# Tray2_BCR.net
KiCad netlist of a schematic drawn in Altium Designer
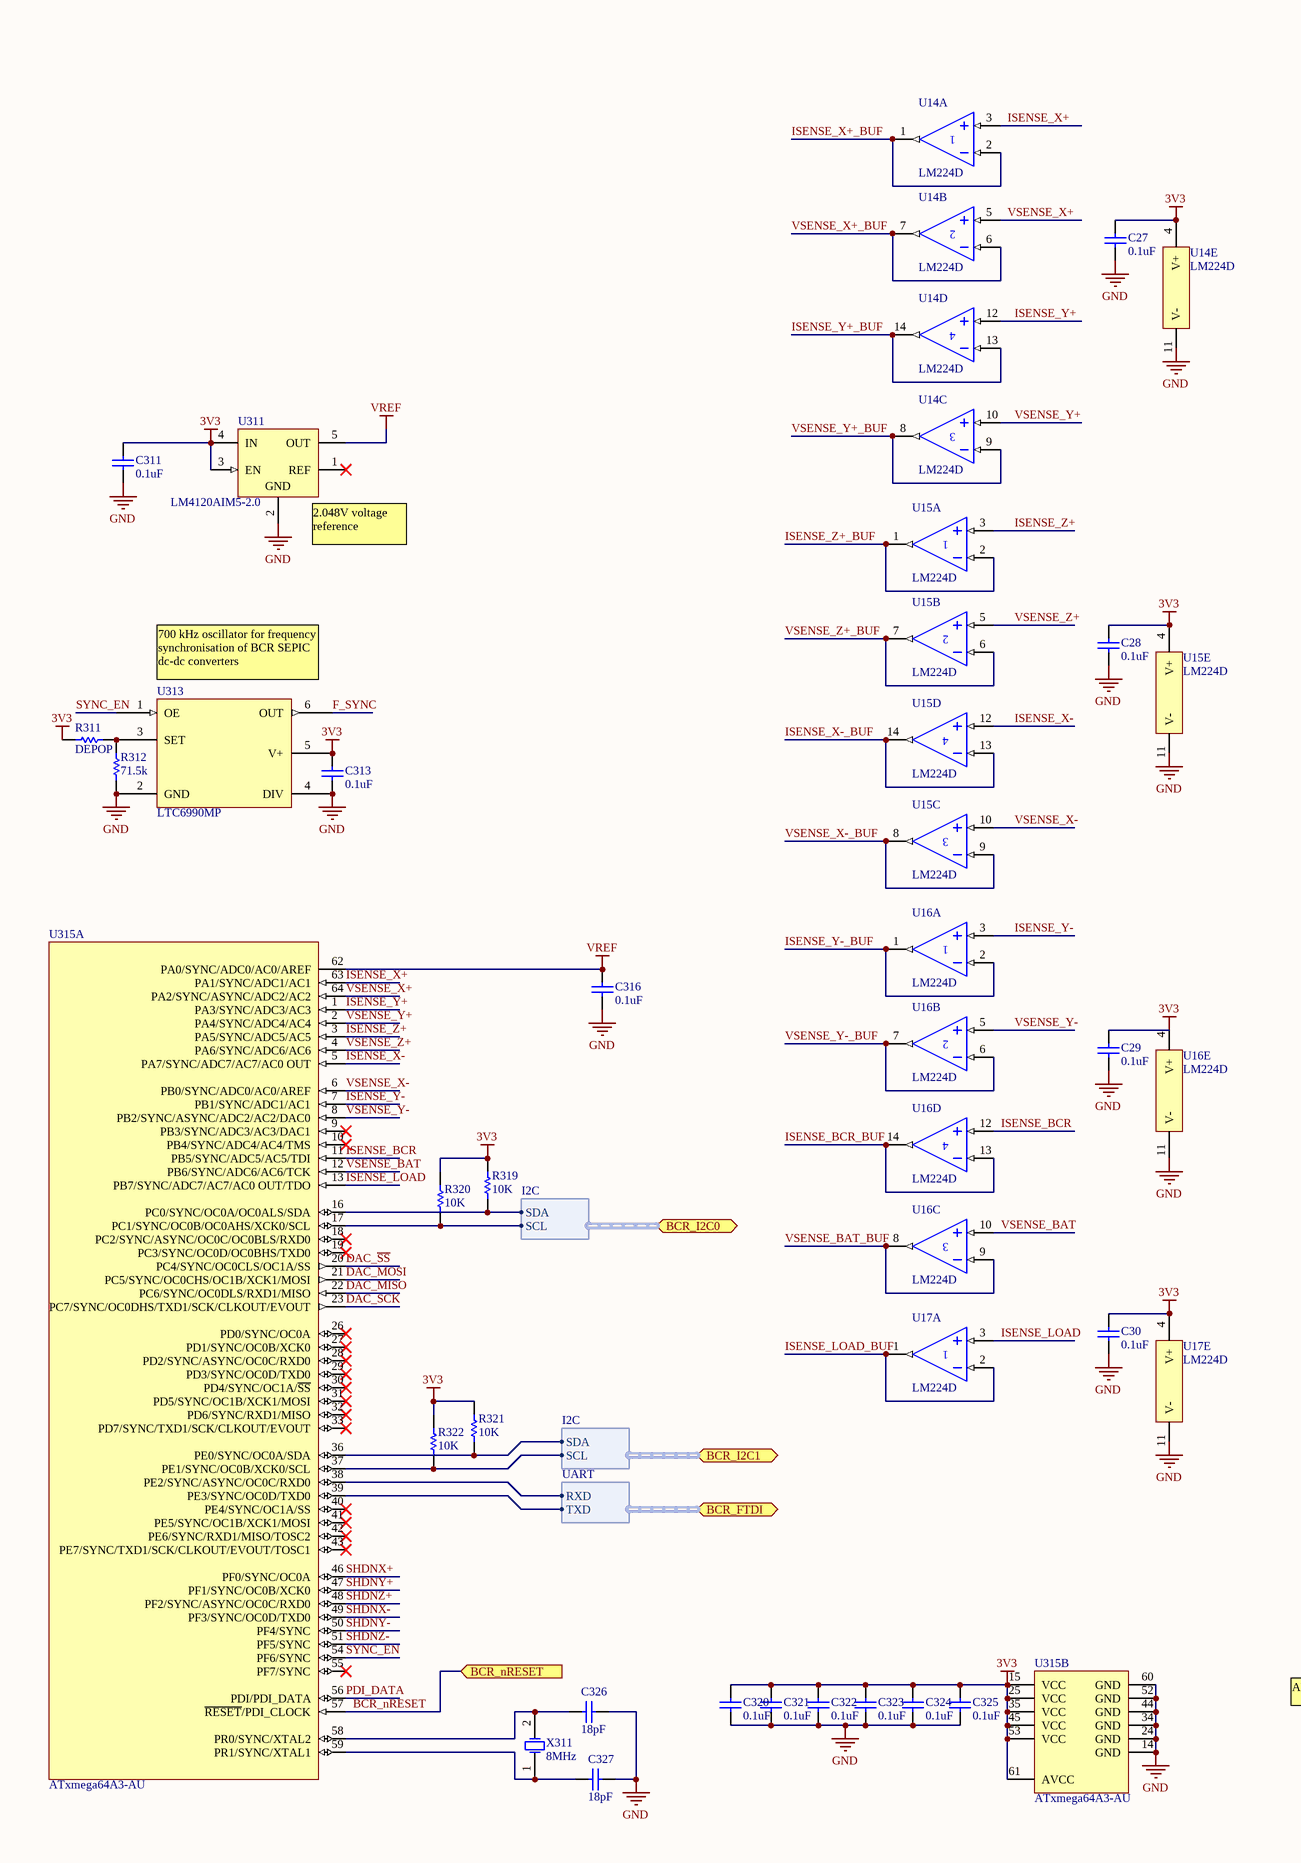
[diagram p0: Tray2_BCR.SchDoc, left]
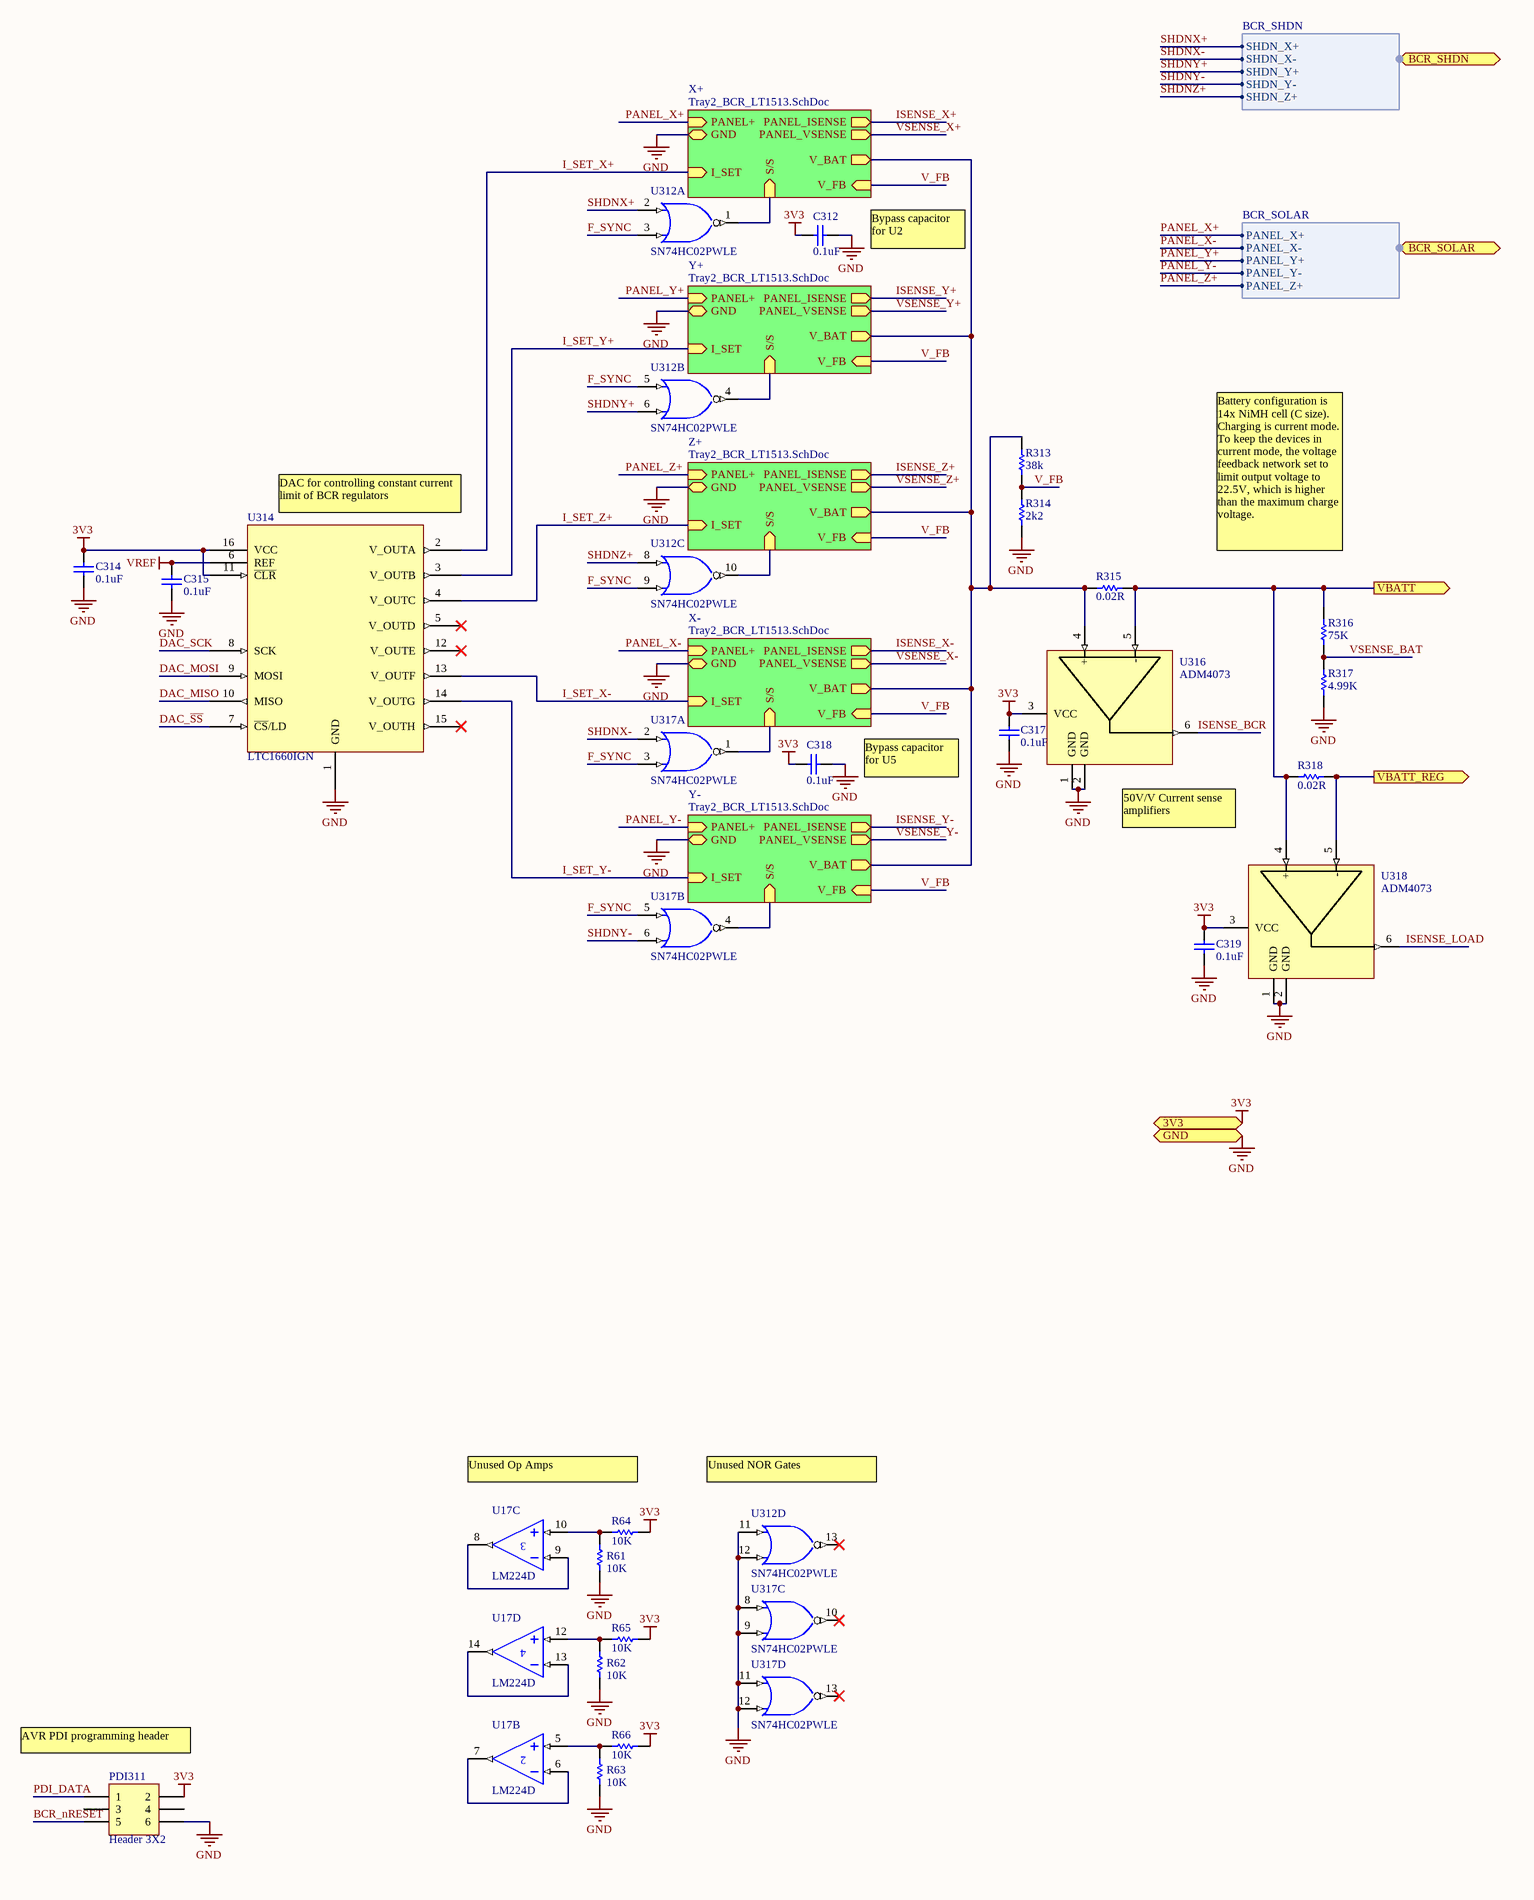
[diagram p1: Tray2_BCR.SchDoc, right]

(export (version "E")
  (design (tool "Eeschema 10.0.6"))
  (components
    (comp (ref "C27")
      (value "0.1uF")
      (footprint "CAPC2012M")
      (description "Capacitor")
      (fields (field (name "Comment") "Cap") (field (name "PUBLISHER") "Altium Limited"))
      (libsource (lib "Miscellaneous Devices") (part "Cap"))
    )
    (comp (ref "C28")
      (value "0.1uF")
      (footprint "CAPC2012M")
      (description "Capacitor")
      (fields (field (name "Comment") "Cap") (field (name "PUBLISHER") "Altium Limited"))
      (libsource (lib "Miscellaneous Devices") (part "Cap"))
    )
    (comp (ref "C29")
      (value "0.1uF")
      (footprint "CAPC2012M")
      (description "Capacitor")
      (fields (field (name "Comment") "Cap") (field (name "PUBLISHER") "Altium Limited"))
      (libsource (lib "Miscellaneous Devices") (part "Cap"))
    )
    (comp (ref "C30")
      (value "0.1uF")
      (footprint "CAPC2012M")
      (description "Capacitor")
      (fields (field (name "Comment") "Cap") (field (name "PUBLISHER") "Altium Limited"))
      (libsource (lib "Miscellaneous Devices") (part "Cap"))
    )
    (comp (ref "C311")
      (value "0.1uF")
      (footprint "CAPC2012M")
      (description "Capacitor")
      (fields (field (name "Comment") "Cap") (field (name "PUBLISHER") "Altium Limited"))
      (libsource (lib "Miscellaneous Devices") (part "Cap"))
    )
    (comp (ref "C312")
      (value "0.1uF")
      (footprint "CAPC2012M")
      (description "Capacitor")
      (fields (field (name "Comment") "Cap") (field (name "PUBLISHER") "Altium Limited"))
      (libsource (lib "Miscellaneous Devices") (part "Cap"))
    )
    (comp (ref "C313")
      (value "0.1uF")
      (footprint "CAPC2012M")
      (description "Capacitor")
      (fields (field (name "Comment") "Cap") (field (name "PUBLISHER") "Altium Limited"))
      (libsource (lib "Miscellaneous Devices") (part "Cap"))
    )
    (comp (ref "C314")
      (value "0.1uF")
      (footprint "CAPC2012M")
      (description "Capacitor")
      (fields (field (name "Comment") "Cap") (field (name "PUBLISHER") "Altium Limited"))
      (libsource (lib "Miscellaneous Devices") (part "Cap"))
    )
    (comp (ref "C315")
      (value "0.1uF")
      (footprint "CAPC2012M")
      (description "Capacitor")
      (fields (field (name "Comment") "Cap") (field (name "PUBLISHER") "Altium Limited"))
      (libsource (lib "Miscellaneous Devices") (part "Cap"))
    )
    (comp (ref "C316")
      (value "0.1uF")
      (footprint "CAPC2012M")
      (description "Capacitor")
      (fields (field (name "Comment") "Cap") (field (name "PUBLISHER") "Altium Limited"))
      (libsource (lib "Miscellaneous Devices") (part "Cap"))
    )
    (comp (ref "C317")
      (value "0.1uF")
      (footprint "CAPC2012M")
      (description "Capacitor")
      (fields (field (name "Comment") "Cap") (field (name "PUBLISHER") "Altium Limited"))
      (libsource (lib "Miscellaneous Devices") (part "Cap"))
    )
    (comp (ref "C318")
      (value "0.1uF")
      (footprint "CAPC2012M")
      (description "Capacitor")
      (fields (field (name "Comment") "Cap") (field (name "PUBLISHER") "Altium Limited"))
      (libsource (lib "Miscellaneous Devices") (part "Cap"))
    )
    (comp (ref "C319")
      (value "0.1uF")
      (footprint "CAPC2012M")
      (description "Capacitor")
      (fields (field (name "Comment") "Cap") (field (name "PUBLISHER") "Altium Limited"))
      (libsource (lib "Miscellaneous Devices") (part "Cap"))
    )
    (comp (ref "C320")
      (value "0.1uF")
      (footprint "CAPC2012M")
      (description "Capacitor")
      (fields (field (name "Comment") "Cap") (field (name "PUBLISHER") "Altium Limited"))
      (libsource (lib "Miscellaneous Devices") (part "Cap"))
    )
    (comp (ref "C321")
      (value "0.1uF")
      (footprint "CAPC2012M")
      (description "Capacitor")
      (fields (field (name "Comment") "Cap") (field (name "PUBLISHER") "Altium Limited"))
      (libsource (lib "Miscellaneous Devices") (part "Cap"))
    )
    (comp (ref "C322")
      (value "0.1uF")
      (footprint "CAPC2012M")
      (description "Capacitor")
      (fields (field (name "Comment") "Cap") (field (name "PUBLISHER") "Altium Limited"))
      (libsource (lib "Miscellaneous Devices") (part "Cap"))
    )
    (comp (ref "C323")
      (value "0.1uF")
      (footprint "CAPC2012M")
      (description "Capacitor")
      (fields (field (name "Comment") "Cap") (field (name "PUBLISHER") "Altium Limited"))
      (libsource (lib "Miscellaneous Devices") (part "Cap"))
    )
    (comp (ref "C324")
      (value "0.1uF")
      (footprint "CAPC2012M")
      (description "Capacitor")
      (fields (field (name "Comment") "Cap") (field (name "PUBLISHER") "Altium Limited"))
      (libsource (lib "Miscellaneous Devices") (part "Cap"))
    )
    (comp (ref "C325")
      (value "0.1uF")
      (footprint "CAPC2012M")
      (description "Capacitor")
      (fields (field (name "Comment") "Cap") (field (name "PUBLISHER") "Altium Limited"))
      (libsource (lib "Miscellaneous Devices") (part "Cap"))
    )
    (comp (ref "C326")
      (value "18pF")
      (footprint "CAPC2012M")
      (description "Capacitor")
      (fields (field (name "Comment") "Cap") (field (name "PUBLISHER") "Altium Limited"))
      (libsource (lib "Miscellaneous Devices") (part "Cap"))
    )
    (comp (ref "C327")
      (value "18pF")
      (footprint "CAPC2012M")
      (description "Capacitor")
      (fields (field (name "Comment") "Cap") (field (name "PUBLISHER") "Altium Limited"))
      (libsource (lib "Miscellaneous Devices") (part "Cap"))
    )
    (comp (ref "PDI311")
      (value "Header 3X2")
      (footprint "HDR2X3")
      (description "Header, 3-Pin, Dual row")
      (fields (field (name "PUBLISHER") "Altium Limited"))
      (libsource (lib "Miscellaneous Connectors") (part "Header 3X2"))
    )
    (comp (ref "R61")
      (value "10K")
      (footprint "RESC2012M")
      (description "Resistor")
      (fields (field (name "Comment") "Res1") (field (name "PUBLISHER") "Altium Limited"))
      (libsource (lib "Miscellaneous Devices") (part "Res1"))
    )
    (comp (ref "R62")
      (value "10K")
      (footprint "RESC2012M")
      (description "Resistor")
      (fields (field (name "Comment") "Res1") (field (name "PUBLISHER") "Altium Limited"))
      (libsource (lib "Miscellaneous Devices") (part "Res1"))
    )
    (comp (ref "R63")
      (value "10K")
      (footprint "RESC2012M")
      (description "Resistor")
      (fields (field (name "Comment") "Res1") (field (name "PUBLISHER") "Altium Limited"))
      (libsource (lib "Miscellaneous Devices") (part "Res1"))
    )
    (comp (ref "R64")
      (value "10K")
      (footprint "RESC2012M")
      (description "Resistor")
      (fields (field (name "Comment") "Res1") (field (name "PUBLISHER") "Altium Limited"))
      (libsource (lib "Miscellaneous Devices") (part "Res1"))
    )
    (comp (ref "R65")
      (value "10K")
      (footprint "RESC2012M")
      (description "Resistor")
      (fields (field (name "Comment") "Res1") (field (name "PUBLISHER") "Altium Limited"))
      (libsource (lib "Miscellaneous Devices") (part "Res1"))
    )
    (comp (ref "R66")
      (value "10K")
      (footprint "RESC2012M")
      (description "Resistor")
      (fields (field (name "Comment") "Res1") (field (name "PUBLISHER") "Altium Limited"))
      (libsource (lib "Miscellaneous Devices") (part "Res1"))
    )
    (comp (ref "R311")
      (value "DEPOP")
      (footprint "RESC2012M")
      (description "Resistor")
      (fields (field (name "Comment") "Res1") (field (name "PUBLISHER") "Altium Limited"))
      (libsource (lib "Miscellaneous Devices") (part "Res1"))
    )
    (comp (ref "R312")
      (value "71.5k")
      (footprint "RESC2012M")
      (description "Resistor")
      (fields (field (name "Comment") "Res1") (field (name "PUBLISHER") "Altium Limited"))
      (libsource (lib "Miscellaneous Devices") (part "Res1"))
    )
    (comp (ref "R313")
      (value "38k")
      (footprint "RESC2012M")
      (description "Resistor")
      (fields (field (name "Comment") "Res1") (field (name "PUBLISHER") "Altium Limited"))
      (libsource (lib "Miscellaneous Devices") (part "Res1"))
    )
    (comp (ref "R314")
      (value "2k2")
      (footprint "RESC2012M")
      (description "Resistor")
      (fields (field (name "Comment") "Res1") (field (name "PUBLISHER") "Altium Limited"))
      (libsource (lib "Miscellaneous Devices") (part "Res1"))
    )
    (comp (ref "R315")
      (value "0.02R")
      (footprint "RESC2012M")
      (description "Resistor")
      (fields (field (name "Comment") "0805 Resistor") (field (name "PUBLISHER") "Altium Limited"))
      (libsource (lib "Miscellaneous Devices") (part "Res1"))
    )
    (comp (ref "R316")
      (value "75K")
      (footprint "RESC2012M")
      (description "Resistor")
      (fields (field (name "Comment") "Res1") (field (name "PUBLISHER") "Altium Limited"))
      (libsource (lib "Miscellaneous Devices") (part "Res1"))
    )
    (comp (ref "R317")
      (value "4.99K")
      (footprint "RESC2012M")
      (description "Resistor")
      (fields (field (name "Comment") "Res1") (field (name "PUBLISHER") "Altium Limited"))
      (libsource (lib "Miscellaneous Devices") (part "Res1"))
    )
    (comp (ref "R318")
      (value "0.02R")
      (footprint "RESC2012M")
      (description "Resistor")
      (fields (field (name "Comment") "0805 Resistor") (field (name "PUBLISHER") "Altium Limited"))
      (libsource (lib "Miscellaneous Devices") (part "Res1"))
    )
    (comp (ref "R319")
      (value "10K")
      (footprint "RESC2012M")
      (description "Resistor")
      (fields (field (name "Comment") "Res1") (field (name "PUBLISHER") "Altium Limited"))
      (libsource (lib "Miscellaneous Devices") (part "Res1"))
    )
    (comp (ref "R320")
      (value "10K")
      (footprint "RESC2012M")
      (description "Resistor")
      (fields (field (name "Comment") "Res1") (field (name "PUBLISHER") "Altium Limited"))
      (libsource (lib "Miscellaneous Devices") (part "Res1"))
    )
    (comp (ref "R321")
      (value "10K")
      (footprint "RESC2012M")
      (description "Resistor")
      (fields (field (name "Comment") "Res1") (field (name "PUBLISHER") "Altium Limited"))
      (libsource (lib "Miscellaneous Devices") (part "Res1"))
    )
    (comp (ref "R322")
      (value "10K")
      (footprint "RESC2012M")
      (description "Resistor")
      (fields (field (name "Comment") "Res1") (field (name "PUBLISHER") "Altium Limited"))
      (libsource (lib "Miscellaneous Devices") (part "Res1"))
    )
    (comp (ref "U14")
      (value "LM224D")
      (footprint "D014_N")
      (description "Quadruple Operational Amplifier")
      (fields (field (name "PUBLISHER") "Altium Limited"))
      (libsource (lib "Tray2") (part "LM224D"))
    )
    (comp (ref "U15")
      (value "LM224D")
      (footprint "D014_N")
      (description "Quadruple Operational Amplifier")
      (fields (field (name "PUBLISHER") "Altium Limited"))
      (libsource (lib "Tray2") (part "LM224D"))
    )
    (comp (ref "U16")
      (value "LM224D")
      (footprint "D014_N")
      (description "Quadruple Operational Amplifier")
      (fields (field (name "PUBLISHER") "Altium Limited"))
      (libsource (lib "Tray2") (part "LM224D"))
    )
    (comp (ref "U17")
      (value "LM224D")
      (footprint "D014_N")
      (description "Quadruple Operational Amplifier")
      (fields (field (name "PUBLISHER") "Altium Limited"))
      (libsource (lib "") (part "LM224D_1"))
    )
    (comp (ref "U311")
      (value "LM4120AIM5-2.0")
      (footprint "MF05A_N")
      (description "Precision Micropower Low Dropout Voltage Reference")
      (fields
        (field (name "MANUFACTURER") "National Semiconductor")
        (field (name "DIGIKEYPARTNUMBER") "LM4120AIM5-2.0CT-ND")
        (field (name "PUBLISHER") "Altium Limited")
      )
      (libsource (lib "NSC Voltage Reference") (part "LM4120AIM5-2.0"))
    )
    (comp (ref "U312")
      (value "SN74HC02PWLE")
      (footprint "TSOP65P640-14AN")
      (description "Quadruple 2-Input Positive-NOR Gate")
      (fields (field (name "PUBLISHER") "Altium Limited"))
      (libsource (lib "TI Logic Gate 2") (part "SN74HC02PWLE"))
    )
    (comp (ref "U313") (value "LTC6990MP") (footprint "SOT26A-6L") (libsource (lib "BCR") (part "LTC6990MP")))
    (comp (ref "U314")
      (value "LTC1660IGN")
      (footprint "SOP635P600-16N")
      (libsource (lib "BCR") (part "LTC1660IGN"))
    )
    (comp (ref "U315")
      (value "ATxmega64A3-AU")
      (footprint "64A_N")
      (libsource (lib "Atmel Microcontroller AVR XMEGA") (part "ATxmega64A3-AU"))
    )
    (comp (ref "U316")
      (value "ADM4073")
      (footprint "SOT26A-6N")
      (description "Current Sense Amplifer")
      (libsource (lib "Schlib1") (part "ADM4073"))
    )
    (comp (ref "U317")
      (value "SN74HC02PWLE")
      (footprint "TSOP65P640-14AN")
      (description "Quadruple 2-Input Positive-NOR Gate")
      (fields (field (name "PUBLISHER") "Altium Limited"))
      (libsource (lib "TI Logic Gate 2") (part "SN74HC02PWLE"))
    )
    (comp (ref "U318")
      (value "ADM4073")
      (footprint "SOT26A-6N")
      (description "Current Sense Amplifer")
      (libsource (lib "Schlib1") (part "ADM4073"))
    )
    (comp (ref "X311")
      (value "8MHz")
      (footprint "HC49 - No border")
      (description "Crystal Oscillator")
      (fields (field (name "PUBLISHER") "Altium Limited"))
      (libsource (lib "Miscellaneous Devices") (part "XTAL"))
    )
  )
  (nets
    (net (code "5") (name "/BCR_nRESET") (class "Default")
      (node (ref "PDI311") (pin "5") (pinfunction "5_5") (pintype "passive"))
      (node (ref "U315") (pin "57") (pinfunction "~{RESET}/PDI_CLOCK_57") (pintype "input"))
    )
    (net (code "6") (name "/DAC_MISO") (class "Default")
      (node (ref "U314") (pin "10") (pinfunction "MISO_10") (pintype "output"))
      (node (ref "U315") (pin "22") (pinfunction "PC6/SYNC/OC0DLS/RXD1/MISO_22") (pintype "input"))
    )
    (net (code "7") (name "/DAC_MOSI") (class "Default")
      (node (ref "U314") (pin "9") (pinfunction "MOSI_9") (pintype "input"))
      (node (ref "U315") (pin "21") (pinfunction "PC5/SYNC/OC0CHS/OC1B/XCK1/MOSI_21") (pintype "output"))
    )
    (net (code "8") (name "/DAC_SCK") (class "Default")
      (node (ref "U314") (pin "8") (pinfunction "SCK_8") (pintype "input"))
      (node (ref "U315") (pin "23") (pinfunction "PC7/SYNC/OC0DHS/TXD1/SCK/CLKOUT/EVOUT_23") (pintype "output"))
    )
    (net (code "9") (name "/DAC_~{SS}") (class "Default")
      (node (ref "U314") (pin "7") (pinfunction "~{CS}/LD_7") (pintype "input"))
      (node (ref "U315") (pin "20") (pinfunction "PC4/SYNC/OC0CLS/OC1A/SS_20") (pintype "output"))
    )
    (net (code "10") (name "/F_SYNC") (class "Default")
      (node (ref "U312") (pin "3") (pinfunction "B_3") (pintype "input"))
      (node (ref "U312") (pin "5") (pinfunction "A_5") (pintype "input"))
      (node (ref "U312") (pin "9") (pinfunction "B_9") (pintype "input"))
      (node (ref "U313") (pin "6") (pinfunction "OUT_6") (pintype "output"))
      (node (ref "U317") (pin "3") (pinfunction "B_3") (pintype "input"))
      (node (ref "U317") (pin "5") (pinfunction "A_5") (pintype "input"))
    )
    (net (code "11") (name "/ISENSE_BCR") (class "Default")
      (node (ref "U16") (pin "12") (pinfunction "IN+_12") (pintype "input"))
      (node (ref "U315") (pin "11") (pinfunction "PB5/SYNC/ADC5/AC5/TDI_11") (pintype "input"))
      (node (ref "U316") (pin "6") (pintype "output"))
    )
    (net (code "12") (name "/ISENSE_BCR_BUF") (class "Default")
      (node (ref "U16") (pin "13") (pinfunction "IN-_13") (pintype "input"))
      (node (ref "U16") (pin "14") (pinfunction "OUT_14") (pintype "output"))
    )
    (net (code "13") (name "/ISENSE_LOAD") (class "Default")
      (node (ref "U17") (pin "3") (pinfunction "IN+_3") (pintype "input"))
      (node (ref "U315") (pin "13") (pinfunction "PB7/SYNC/ADC7/AC7/AC0_OUT/TDO_13") (pintype "input"))
      (node (ref "U318") (pin "6") (pintype "output"))
    )
    (net (code "14") (name "/ISENSE_LOAD_BUF") (class "Default")
      (node (ref "U17") (pin "1") (pinfunction "OUT_1") (pintype "output"))
      (node (ref "U17") (pin "2") (pinfunction "IN-_2") (pintype "input"))
    )
    (net (code "15") (name "/ISENSE_X+") (class "Default")
      (node (ref "U14") (pin "3") (pinfunction "IN+_3") (pintype "input"))
      (node (ref "U315") (pin "63") (pinfunction "PA1/SYNC/ADC1/AC1_63") (pintype "input"))
    )
    (net (code "16") (name "/ISENSE_X+_BUF") (class "Default")
      (node (ref "U14") (pin "1") (pinfunction "OUT_1") (pintype "output"))
      (node (ref "U14") (pin "2") (pinfunction "IN-_2") (pintype "input"))
    )
    (net (code "17") (name "/ISENSE_X-") (class "Default")
      (node (ref "U15") (pin "12") (pinfunction "IN+_12") (pintype "input"))
      (node (ref "U315") (pin "5") (pinfunction "PA7/SYNC/ADC7/AC7/AC0_OUT_5") (pintype "input"))
    )
    (net (code "18") (name "/ISENSE_X-_BUF") (class "Default")
      (node (ref "U15") (pin "13") (pinfunction "IN-_13") (pintype "input"))
      (node (ref "U15") (pin "14") (pinfunction "OUT_14") (pintype "output"))
    )
    (net (code "19") (name "/ISENSE_Y+") (class "Default")
      (node (ref "U14") (pin "12") (pinfunction "IN+_12") (pintype "input"))
      (node (ref "U315") (pin "1") (pinfunction "PA3/SYNC/ADC3/AC3_1") (pintype "input"))
    )
    (net (code "20") (name "/ISENSE_Y+_BUF") (class "Default")
      (node (ref "U14") (pin "13") (pinfunction "IN-_13") (pintype "input"))
      (node (ref "U14") (pin "14") (pinfunction "OUT_14") (pintype "output"))
    )
    (net (code "21") (name "/ISENSE_Y-") (class "Default")
      (node (ref "U16") (pin "3") (pinfunction "IN+_3") (pintype "input"))
      (node (ref "U315") (pin "7") (pinfunction "PB1/SYNC/ADC1/AC1_7") (pintype "input"))
    )
    (net (code "22") (name "/ISENSE_Y-_BUF") (class "Default")
      (node (ref "U16") (pin "1") (pinfunction "OUT_1") (pintype "output"))
      (node (ref "U16") (pin "2") (pinfunction "IN-_2") (pintype "input"))
    )
    (net (code "23") (name "/ISENSE_Z+") (class "Default")
      (node (ref "U15") (pin "3") (pinfunction "IN+_3") (pintype "input"))
      (node (ref "U315") (pin "3") (pinfunction "PA5/SYNC/ADC5/AC5_3") (pintype "input"))
    )
    (net (code "24") (name "/ISENSE_Z+_BUF") (class "Default")
      (node (ref "U15") (pin "1") (pinfunction "OUT_1") (pintype "output"))
      (node (ref "U15") (pin "2") (pinfunction "IN-_2") (pintype "input"))
    )
    (net (code "25") (name "/I_SET_X+") (class "Default")
      (node (ref "U314") (pin "2") (pinfunction "V_OUTA_2") (pintype "output"))
    )
    (net (code "26") (name "/I_SET_X-") (class "Default")
      (node (ref "U314") (pin "13") (pinfunction "V_OUTF_13") (pintype "output"))
    )
    (net (code "27") (name "/I_SET_Y+") (class "Default")
      (node (ref "U314") (pin "3") (pinfunction "V_OUTB_3") (pintype "output"))
    )
    (net (code "28") (name "/I_SET_Y-") (class "Default")
      (node (ref "U314") (pin "14") (pinfunction "V_OUTG_14") (pintype "output"))
    )
    (net (code "29") (name "/I_SET_Z+") (class "Default")
      (node (ref "U314") (pin "4") (pinfunction "V_OUTC_4") (pintype "output"))
    )
    (net (code "35") (name "/PDI_DATA") (class "Default")
      (node (ref "PDI311") (pin "1") (pinfunction "1_1") (pintype "passive"))
      (node (ref "U315") (pin "56") (pinfunction "PDI/PDI_DATA_56") (pintype "bidirectional"))
    )
    (net (code "36") (name "/SHDNX+") (class "Default")
      (node (ref "U312") (pin "2") (pinfunction "A_2") (pintype "input"))
      (node (ref "U315") (pin "46") (pinfunction "PF0/SYNC/OC0A_46") (pintype "bidirectional"))
    )
    (net (code "37") (name "/SHDNX-") (class "Default")
      (node (ref "U315") (pin "49") (pinfunction "PF3/SYNC/OC0D/TXD0_49") (pintype "bidirectional"))
      (node (ref "U317") (pin "2") (pinfunction "A_2") (pintype "input"))
    )
    (net (code "38") (name "/SHDNY+") (class "Default")
      (node (ref "U312") (pin "6") (pinfunction "B_6") (pintype "input"))
      (node (ref "U315") (pin "47") (pinfunction "PF1/SYNC/OC0B/XCK0_47") (pintype "bidirectional"))
    )
    (net (code "39") (name "/SHDNY-") (class "Default")
      (node (ref "U315") (pin "50") (pinfunction "PF4/SYNC_50") (pintype "bidirectional"))
      (node (ref "U317") (pin "6") (pinfunction "B_6") (pintype "input"))
    )
    (net (code "40") (name "/SHDNZ+") (class "Default")
      (node (ref "U312") (pin "8") (pinfunction "A_8") (pintype "input"))
      (node (ref "U315") (pin "48") (pinfunction "PF2/SYNC/ASYNC/OC0C/RXD0_48") (pintype "bidirectional"))
    )
    (net (code "41") (name "/SHDNZ-") (class "Default")
      (node (ref "U315") (pin "51") (pinfunction "PF5/SYNC_51") (pintype "bidirectional"))
    )
    (net (code "42") (name "/SYNC_EN") (class "Default")
      (node (ref "U313") (pin "1") (pinfunction "OE_1") (pintype "input"))
      (node (ref "U315") (pin "54") (pinfunction "PF6/SYNC_54") (pintype "bidirectional"))
    )
    (net (code "43") (name "/S{slash}S") (class "Default")
      (node (ref "U317") (pin "4") (pinfunction "Y_4") (pintype "output"))
    )
    (net (code "44") (name "/S{slash}S_1") (class "Default")
      (node (ref "U312") (pin "1") (pinfunction "Y_1") (pintype "output"))
    )
    (net (code "45") (name "/S{slash}S_2") (class "Default")
      (node (ref "U312") (pin "4") (pinfunction "Y_4") (pintype "output"))
    )
    (net (code "46") (name "/S{slash}S_3") (class "Default")
      (node (ref "U312") (pin "10") (pinfunction "Y_10") (pintype "output"))
    )
    (net (code "47") (name "/S{slash}S_4") (class "Default")
      (node (ref "U317") (pin "1") (pinfunction "Y_1") (pintype "output"))
    )
    (net (code "48") (name "/VBATT") (class "Default")
      (node (ref "R315") (pin "2") (pinfunction "2_2") (pintype "passive"))
      (node (ref "R316") (pin "1") (pinfunction "1_1") (pintype "passive"))
      (node (ref "R318") (pin "2") (pinfunction "2_2") (pintype "passive"))
      (node (ref "U316") (pin "5") (pinfunction "-_5") (pintype "input"))
      (node (ref "U318") (pin "4") (pinfunction "+_4") (pintype "input"))
    )
    (net (code "49") (name "/VBATT_REG") (class "Default")
      (node (ref "R318") (pin "1") (pinfunction "1_1") (pintype "passive"))
      (node (ref "U318") (pin "5") (pinfunction "-_5") (pintype "input"))
    )
    (net (code "50") (name "/VSENSE_BAT") (class "Default")
      (node (ref "R316") (pin "2") (pinfunction "2_2") (pintype "passive"))
      (node (ref "R317") (pin "1") (pinfunction "1_1") (pintype "passive"))
      (node (ref "U16") (pin "10") (pinfunction "IN+_10") (pintype "input"))
      (node (ref "U315") (pin "12") (pinfunction "PB6/SYNC/ADC6/AC6/TCK_12") (pintype "input"))
    )
    (net (code "51") (name "/VSENSE_BAT_BUF") (class "Default")
      (node (ref "U16") (pin "8") (pinfunction "OUT_8") (pintype "output"))
      (node (ref "U16") (pin "9") (pinfunction "IN-_9") (pintype "input"))
    )
    (net (code "52") (name "/VSENSE_X+") (class "Default")
      (node (ref "U14") (pin "5") (pinfunction "IN+_5") (pintype "input"))
      (node (ref "U315") (pin "64") (pinfunction "PA2/SYNC/ASYNC/ADC2/AC2_64") (pintype "input"))
    )
    (net (code "53") (name "/VSENSE_X+_BUF") (class "Default")
      (node (ref "U14") (pin "6") (pinfunction "IN-_6") (pintype "input"))
      (node (ref "U14") (pin "7") (pinfunction "OUT_7") (pintype "output"))
    )
    (net (code "54") (name "/VSENSE_X-") (class "Default")
      (node (ref "U15") (pin "10") (pinfunction "IN+_10") (pintype "input"))
      (node (ref "U315") (pin "6") (pinfunction "PB0/SYNC/ADC0/AC0/AREF_6") (pintype "input"))
    )
    (net (code "55") (name "/VSENSE_X-_BUF") (class "Default")
      (node (ref "U15") (pin "8") (pinfunction "OUT_8") (pintype "output"))
      (node (ref "U15") (pin "9") (pinfunction "IN-_9") (pintype "input"))
    )
    (net (code "56") (name "/VSENSE_Y+") (class "Default")
      (node (ref "U14") (pin "10") (pinfunction "IN+_10") (pintype "input"))
      (node (ref "U315") (pin "2") (pinfunction "PA4/SYNC/ADC4/AC4_2") (pintype "input"))
    )
    (net (code "57") (name "/VSENSE_Y+_BUF") (class "Default")
      (node (ref "U14") (pin "8") (pinfunction "OUT_8") (pintype "output"))
      (node (ref "U14") (pin "9") (pinfunction "IN-_9") (pintype "input"))
    )
    (net (code "58") (name "/VSENSE_Y-") (class "Default")
      (node (ref "U16") (pin "5") (pinfunction "IN+_5") (pintype "input"))
      (node (ref "U315") (pin "8") (pinfunction "PB2/SYNC/ASYNC/ADC2/AC2/DAC0_8") (pintype "input"))
    )
    (net (code "59") (name "/VSENSE_Y-_BUF") (class "Default")
      (node (ref "U16") (pin "6") (pinfunction "IN-_6") (pintype "input"))
      (node (ref "U16") (pin "7") (pinfunction "OUT_7") (pintype "output"))
    )
    (net (code "60") (name "/VSENSE_Z+") (class "Default")
      (node (ref "U15") (pin "5") (pinfunction "IN+_5") (pintype "input"))
      (node (ref "U315") (pin "4") (pinfunction "PA6/SYNC/ADC6/AC6_4") (pintype "input"))
    )
    (net (code "61") (name "/VSENSE_Z+_BUF") (class "Default")
      (node (ref "U15") (pin "6") (pinfunction "IN-_6") (pintype "input"))
      (node (ref "U15") (pin "7") (pinfunction "OUT_7") (pintype "output"))
    )
    (net (code "62") (name "/V_BAT") (class "Default")
      (node (ref "R313") (pin "2") (pinfunction "2_2") (pintype "passive"))
      (node (ref "R315") (pin "1") (pinfunction "1_1") (pintype "passive"))
      (node (ref "U316") (pin "4") (pinfunction "+_4") (pintype "input"))
    )
    (net (code "63") (name "/V_FB") (class "Default")
      (node (ref "R313") (pin "1") (pinfunction "1_1") (pintype "passive"))
      (node (ref "R314") (pin "2") (pinfunction "2_2") (pintype "passive"))
    )
    (net (code "68") (name "3V3") (class "Default")
      (node (ref "C27") (pin "1") (pinfunction "1_1") (pintype "passive"))
      (node (ref "C28") (pin "1") (pinfunction "1_1") (pintype "passive"))
      (node (ref "C29") (pin "1") (pinfunction "1_1") (pintype "passive"))
      (node (ref "C30") (pin "1") (pinfunction "1_1") (pintype "passive"))
      (node (ref "C311") (pin "2") (pinfunction "2_2") (pintype "passive"))
      (node (ref "C312") (pin "2") (pinfunction "2_2") (pintype "passive"))
      (node (ref "C313") (pin "1") (pinfunction "1_1") (pintype "passive"))
      (node (ref "C314") (pin "2") (pinfunction "2_2") (pintype "passive"))
      (node (ref "C317") (pin "1") (pinfunction "1_1") (pintype "passive"))
      (node (ref "C318") (pin "2") (pinfunction "2_2") (pintype "passive"))
      (node (ref "C319") (pin "1") (pinfunction "1_1") (pintype "passive"))
      (node (ref "C320") (pin "2") (pinfunction "2_2") (pintype "passive"))
      (node (ref "C321") (pin "2") (pinfunction "2_2") (pintype "passive"))
      (node (ref "C322") (pin "2") (pinfunction "2_2") (pintype "passive"))
      (node (ref "C323") (pin "2") (pinfunction "2_2") (pintype "passive"))
      (node (ref "C324") (pin "2") (pinfunction "2_2") (pintype "passive"))
      (node (ref "C325") (pin "2") (pinfunction "2_2") (pintype "passive"))
      (node (ref "PDI311") (pin "2") (pinfunction "2_2") (pintype "passive"))
      (node (ref "R311") (pin "1") (pinfunction "1_1") (pintype "passive"))
      (node (ref "R319") (pin "1") (pinfunction "1_1") (pintype "passive"))
      (node (ref "R320") (pin "1") (pinfunction "1_1") (pintype "passive"))
      (node (ref "R321") (pin "1") (pinfunction "1_1") (pintype "passive"))
      (node (ref "R322") (pin "1") (pinfunction "1_1") (pintype "passive"))
      (node (ref "R64") (pin "2") (pinfunction "2_2") (pintype "passive"))
      (node (ref "R65") (pin "2") (pinfunction "2_2") (pintype "passive"))
      (node (ref "R66") (pin "2") (pinfunction "2_2") (pintype "passive"))
      (node (ref "U14") (pin "4") (pinfunction "V+_4") (pintype "power_in"))
      (node (ref "U15") (pin "4") (pinfunction "V+_4") (pintype "power_in"))
      (node (ref "U17") (pin "4") (pinfunction "V+_4") (pintype "power_in"))
      (node (ref "U311") (pin "3") (pinfunction "EN_3") (pintype "input"))
      (node (ref "U311") (pin "4") (pinfunction "IN_4") (pintype "power_in"))
      (node (ref "U313") (pin "5") (pinfunction "V+_5") (pintype "passive"))
      (node (ref "U314") (pin "11") (pinfunction "~{CLR}_11") (pintype "input"))
      (node (ref "U314") (pin "16") (pinfunction "VCC_16") (pintype "passive"))
      (node (ref "U315") (pin "15") (pinfunction "VCC_15") (pintype "power_in"))
      (node (ref "U315") (pin "25") (pinfunction "VCC_25") (pintype "power_in"))
      (node (ref "U315") (pin "35") (pinfunction "VCC_35") (pintype "power_in"))
      (node (ref "U315") (pin "45") (pinfunction "VCC_45") (pintype "power_in"))
      (node (ref "U315") (pin "53") (pinfunction "VCC_53") (pintype "power_in"))
      (node (ref "U315") (pin "61") (pinfunction "AVCC_61") (pintype "power_in"))
      (node (ref "U316") (pin "3") (pinfunction "VCC_3") (pintype "passive"))
      (node (ref "U318") (pin "3") (pinfunction "VCC_3") (pintype "passive"))
    )
    (net (code "69") (name "GND") (class "Default")
      (node (ref "C27") (pin "2") (pinfunction "2_2") (pintype "passive"))
      (node (ref "C28") (pin "2") (pinfunction "2_2") (pintype "passive"))
      (node (ref "C29") (pin "2") (pinfunction "2_2") (pintype "passive"))
      (node (ref "C30") (pin "2") (pinfunction "2_2") (pintype "passive"))
      (node (ref "C311") (pin "1") (pinfunction "1_1") (pintype "passive"))
      (node (ref "C312") (pin "1") (pinfunction "1_1") (pintype "passive"))
      (node (ref "C313") (pin "2") (pinfunction "2_2") (pintype "passive"))
      (node (ref "C314") (pin "1") (pinfunction "1_1") (pintype "passive"))
      (node (ref "C315") (pin "1") (pinfunction "1_1") (pintype "passive"))
      (node (ref "C316") (pin "1") (pinfunction "1_1") (pintype "passive"))
      (node (ref "C317") (pin "2") (pinfunction "2_2") (pintype "passive"))
      (node (ref "C318") (pin "1") (pinfunction "1_1") (pintype "passive"))
      (node (ref "C319") (pin "2") (pinfunction "2_2") (pintype "passive"))
      (node (ref "C320") (pin "1") (pinfunction "1_1") (pintype "passive"))
      (node (ref "C321") (pin "1") (pinfunction "1_1") (pintype "passive"))
      (node (ref "C322") (pin "1") (pinfunction "1_1") (pintype "passive"))
      (node (ref "C323") (pin "1") (pinfunction "1_1") (pintype "passive"))
      (node (ref "C324") (pin "1") (pinfunction "1_1") (pintype "passive"))
      (node (ref "C325") (pin "1") (pinfunction "1_1") (pintype "passive"))
      (node (ref "C326") (pin "2") (pinfunction "2_2") (pintype "passive"))
      (node (ref "C327") (pin "1") (pinfunction "1_1") (pintype "passive"))
      (node (ref "PDI311") (pin "6") (pinfunction "6_6") (pintype "passive"))
      (node (ref "R312") (pin "1") (pinfunction "1_1") (pintype "passive"))
      (node (ref "R314") (pin "1") (pinfunction "1_1") (pintype "passive"))
      (node (ref "R317") (pin "2") (pinfunction "2_2") (pintype "passive"))
      (node (ref "R61") (pin "2") (pinfunction "2_2") (pintype "passive"))
      (node (ref "R62") (pin "2") (pinfunction "2_2") (pintype "passive"))
      (node (ref "R63") (pin "2") (pinfunction "2_2") (pintype "passive"))
      (node (ref "U16") (pin "11") (pinfunction "V-_11") (pintype "power_in"))
      (node (ref "U311") (pin "2") (pinfunction "GND_2") (pintype "power_in"))
      (node (ref "U312") (pin "11") (pinfunction "A_11") (pintype "input"))
      (node (ref "U312") (pin "12") (pinfunction "B_12") (pintype "input"))
      (node (ref "U312") (pin "7") (pinfunction "GND_7") (pintype "power_in"))
      (node (ref "U313") (pin "2") (pinfunction "GND_2") (pintype "passive"))
      (node (ref "U313") (pin "4") (pinfunction "DIV_4") (pintype "passive"))
      (node (ref "U314") (pin "1") (pinfunction "GND_1") (pintype "passive"))
      (node (ref "U315") (pin "14") (pinfunction "GND_14") (pintype "power_in"))
      (node (ref "U315") (pin "24") (pinfunction "GND_24") (pintype "power_in"))
      (node (ref "U315") (pin "34") (pinfunction "GND_34") (pintype "power_in"))
      (node (ref "U315") (pin "44") (pinfunction "GND_44") (pintype "power_in"))
      (node (ref "U315") (pin "52") (pinfunction "GND_52") (pintype "power_in"))
      (node (ref "U315") (pin "60") (pinfunction "GND_60") (pintype "power_in"))
      (node (ref "U316") (pin "1") (pinfunction "GND_1") (pintype "passive"))
      (node (ref "U316") (pin "2") (pinfunction "GND_2") (pintype "passive"))
      (node (ref "U317") (pin "11") (pinfunction "A_11") (pintype "input"))
      (node (ref "U317") (pin "12") (pinfunction "B_12") (pintype "input"))
      (node (ref "U317") (pin "7") (pinfunction "GND_7") (pintype "power_in"))
      (node (ref "U317") (pin "8") (pinfunction "A_8") (pintype "input"))
      (node (ref "U317") (pin "9") (pinfunction "B_9") (pintype "input"))
      (node (ref "U318") (pin "1") (pinfunction "GND_1") (pintype "passive"))
      (node (ref "U318") (pin "2") (pinfunction "GND_2") (pintype "passive"))
    )
    (net (code "70") (name "Net-(U17B-IN+)") (class "Default")
      (node (ref "R63") (pin "1") (pinfunction "1_1") (pintype "passive"))
      (node (ref "R66") (pin "1") (pinfunction "1_1") (pintype "passive"))
      (node (ref "U17") (pin "5") (pinfunction "IN+_5") (pintype "input"))
    )
    (net (code "71") (name "Net-(U17B-IN-)") (class "Default")
      (node (ref "U17") (pin "6") (pinfunction "IN-_6") (pintype "input"))
      (node (ref "U17") (pin "7") (pinfunction "OUT_7") (pintype "output"))
    )
    (net (code "72") (name "Net-(U17C-IN+)") (class "Default")
      (node (ref "R61") (pin "1") (pinfunction "1_1") (pintype "passive"))
      (node (ref "R64") (pin "1") (pinfunction "1_1") (pintype "passive"))
      (node (ref "U17") (pin "10") (pinfunction "IN+_10") (pintype "input"))
    )
    (net (code "73") (name "Net-(U17C-IN-)") (class "Default")
      (node (ref "U17") (pin "8") (pinfunction "OUT_8") (pintype "output"))
      (node (ref "U17") (pin "9") (pinfunction "IN-_9") (pintype "input"))
    )
    (net (code "74") (name "Net-(U17D-IN+)") (class "Default")
      (node (ref "R62") (pin "1") (pinfunction "1_1") (pintype "passive"))
      (node (ref "R65") (pin "1") (pinfunction "1_1") (pintype "passive"))
      (node (ref "U17") (pin "12") (pinfunction "IN+_12") (pintype "input"))
    )
    (net (code "75") (name "Net-(U17D-IN-)") (class "Default")
      (node (ref "U17") (pin "13") (pinfunction "IN-_13") (pintype "input"))
      (node (ref "U17") (pin "14") (pinfunction "OUT_14") (pintype "output"))
    )
    (net (code "76") (name "Net-(U313-SET)") (class "Default")
      (node (ref "R311") (pin "2") (pinfunction "2_2") (pintype "passive"))
      (node (ref "R312") (pin "2") (pinfunction "2_2") (pintype "passive"))
      (node (ref "U313") (pin "3") (pinfunction "SET_3") (pintype "passive"))
    )
    (net (code "77") (name "Net-(U315A-PC0{slash}SYNC{slash}OC0A{slash}OC0ALS{slash}SDA)") (class "Default")
      (node (ref "R319") (pin "2") (pinfunction "2_2") (pintype "passive"))
      (node (ref "U315") (pin "16") (pinfunction "PC0/SYNC/OC0A/OC0ALS/SDA_16") (pintype "bidirectional"))
    )
    (net (code "78") (name "Net-(U315A-PC1{slash}SYNC{slash}OC0B{slash}OC0AHS{slash}XCK0{slash}SCL)") (class "Default")
      (node (ref "R320") (pin "2") (pinfunction "2_2") (pintype "passive"))
      (node (ref "U315") (pin "17") (pinfunction "PC1/SYNC/OC0B/OC0AHS/XCK0/SCL_17") (pintype "bidirectional"))
    )
    (net (code "79") (name "Net-(U315A-PE0{slash}SYNC{slash}OC0A{slash}SDA)") (class "Default")
      (node (ref "R321") (pin "2") (pinfunction "2_2") (pintype "passive"))
      (node (ref "U315") (pin "36") (pinfunction "PE0/SYNC/OC0A/SDA_36") (pintype "bidirectional"))
    )
    (net (code "80") (name "Net-(U315A-PE1{slash}SYNC{slash}OC0B{slash}XCK0{slash}SCL)") (class "Default")
      (node (ref "R322") (pin "2") (pinfunction "2_2") (pintype "passive"))
      (node (ref "U315") (pin "37") (pinfunction "PE1/SYNC/OC0B/XCK0/SCL_37") (pintype "bidirectional"))
    )
    (net (code "81") (name "Net-(U315A-PR0{slash}SYNC{slash}XTAL2)") (class "Default")
      (node (ref "C326") (pin "1") (pinfunction "1_1") (pintype "passive"))
      (node (ref "U315") (pin "58") (pinfunction "PR0/SYNC/XTAL2_58") (pintype "bidirectional"))
      (node (ref "X311") (pin "2") (pinfunction "OSC2_2") (pintype "passive"))
    )
    (net (code "82") (name "Net-(U315A-PR1{slash}SYNC{slash}XTAL1)") (class "Default")
      (node (ref "C327") (pin "2") (pinfunction "2_2") (pintype "passive"))
      (node (ref "U315") (pin "59") (pinfunction "PR1/SYNC/XTAL1_59") (pintype "bidirectional"))
      (node (ref "X311") (pin "1") (pinfunction "OSC1_1") (pintype "passive"))
    )
    (net (code "83") (name "VCC") (class "Default")
      (node (ref "U312") (pin "14") (pinfunction "VCC_14") (pintype "power_in"))
      (node (ref "U317") (pin "14") (pinfunction "VCC_14") (pintype "power_in"))
    )
    (net (code "84") (name "VREF") (class "Default")
      (node (ref "C315") (pin "2") (pinfunction "2_2") (pintype "passive"))
      (node (ref "C316") (pin "2") (pinfunction "2_2") (pintype "passive"))
      (node (ref "U311") (pin "5") (pinfunction "OUT_5") (pintype "power_in"))
      (node (ref "U314") (pin "6") (pinfunction "REF_6") (pintype "passive"))
      (node (ref "U315") (pin "62") (pinfunction "PA0/SYNC/ADC0/AC0/AREF_62") (pintype "passive"))
    )
    (net (code "85") (name "unconnected-(PDI311-Pad3)") (class "Default")
      (node (ref "PDI311") (pin "3") (pinfunction "3_3") (pintype "passive"))
    )
    (net (code "86") (name "unconnected-(PDI311-Pad4)") (class "Default")
      (node (ref "PDI311") (pin "4") (pinfunction "4_4") (pintype "passive"))
    )
    (net (code "87") (name "unconnected-(U14E-V--Pad11)") (class "Default")
      (node (ref "U14") (pin "11") (pinfunction "V-_11") (pintype "power_in"))
    )
    (net (code "88") (name "unconnected-(U15E-V--Pad11)") (class "Default")
      (node (ref "U15") (pin "11") (pinfunction "V-_11") (pintype "power_in"))
    )
    (net (code "89") (name "unconnected-(U16E-V+-Pad4)") (class "Default")
      (node (ref "U16") (pin "4") (pinfunction "V+_4") (pintype "power_in"))
    )
    (net (code "90") (name "unconnected-(U17E-V--Pad11)") (class "Default")
      (node (ref "U17") (pin "11") (pinfunction "V-_11") (pintype "power_in"))
    )
    (net (code "91") (name "unconnected-(U311-REF-Pad1)") (class "Default")
      (node (ref "U311") (pin "1") (pinfunction "REF_1") (pintype "passive+no_connect"))
    )
    (net (code "92") (name "unconnected-(U312D-Y-Pad13)") (class "Default")
      (node (ref "U312") (pin "13") (pinfunction "Y_13") (pintype "output+no_connect"))
    )
    (net (code "93") (name "unconnected-(U314-V_OUTD-Pad5)") (class "Default")
      (node (ref "U314") (pin "5") (pinfunction "V_OUTD_5") (pintype "output+no_connect"))
    )
    (net (code "94") (name "unconnected-(U314-V_OUTE-Pad12)") (class "Default")
      (node (ref "U314") (pin "12") (pinfunction "V_OUTE_12") (pintype "output+no_connect"))
    )
    (net (code "95") (name "unconnected-(U314-V_OUTH-Pad15)") (class "Default")
      (node (ref "U314") (pin "15") (pinfunction "V_OUTH_15") (pintype "output+no_connect"))
    )
    (net (code "96") (name "unconnected-(U315A-PB3{slash}SYNC{slash}ADC3{slash}AC3{slash}DAC1-Pad9)") (class "Default")
      (node (ref "U315") (pin "9") (pinfunction "PB3/SYNC/ADC3/AC3/DAC1_9") (pintype "input+no_connect"))
    )
    (net (code "97") (name "unconnected-(U315A-PB4{slash}SYNC{slash}ADC4{slash}AC4{slash}TMS-Pad10)") (class "Default")
      (node (ref "U315") (pin "10") (pinfunction "PB4/SYNC/ADC4/AC4/TMS_10") (pintype "input+no_connect"))
    )
    (net (code "98") (name "unconnected-(U315A-PC2{slash}SYNC{slash}ASYNC{slash}OC0C{slash}OC0BLS{slash}RXD0-Pad18)") (class "Default")
      (node (ref "U315") (pin "18") (pinfunction "PC2/SYNC/ASYNC/OC0C/OC0BLS/RXD0_18") (pintype "bidirectional+no_connect"))
    )
    (net (code "99") (name "unconnected-(U315A-PC3{slash}SYNC{slash}OC0D{slash}OC0BHS{slash}TXD0-Pad19)") (class "Default")
      (node (ref "U315") (pin "19") (pinfunction "PC3/SYNC/OC0D/OC0BHS/TXD0_19") (pintype "bidirectional+no_connect"))
    )
    (net (code "100") (name "unconnected-(U315A-PD0{slash}SYNC{slash}OC0A-Pad26)") (class "Default")
      (node (ref "U315") (pin "26") (pinfunction "PD0/SYNC/OC0A_26") (pintype "bidirectional+no_connect"))
    )
    (net (code "101") (name "unconnected-(U315A-PD1{slash}SYNC{slash}OC0B{slash}XCK0-Pad27)") (class "Default")
      (node (ref "U315") (pin "27") (pinfunction "PD1/SYNC/OC0B/XCK0_27") (pintype "bidirectional+no_connect"))
    )
    (net (code "102") (name "unconnected-(U315A-PD2{slash}SYNC{slash}ASYNC{slash}OC0C{slash}RXD0-Pad28)") (class "Default")
      (node (ref "U315") (pin "28") (pinfunction "PD2/SYNC/ASYNC/OC0C/RXD0_28") (pintype "bidirectional+no_connect"))
    )
    (net (code "103") (name "unconnected-(U315A-PD3{slash}SYNC{slash}OC0D{slash}TXD0-Pad29)") (class "Default")
      (node (ref "U315") (pin "29") (pinfunction "PD3/SYNC/OC0D/TXD0_29") (pintype "bidirectional+no_connect"))
    )
    (net (code "104") (name "unconnected-(U315A-PD4{slash}SYNC{slash}OC1A{slash}~{SS}-Pad30)") (class "Default")
      (node (ref "U315") (pin "30") (pinfunction "PD4/SYNC/OC1A/~{SS}_30") (pintype "bidirectional+no_connect"))
    )
    (net (code "105") (name "unconnected-(U315A-PD5{slash}SYNC{slash}OC1B{slash}XCK1{slash}MOSI-Pad31)") (class "Default")
      (node (ref "U315") (pin "31") (pinfunction "PD5/SYNC/OC1B/XCK1/MOSI_31") (pintype "bidirectional+no_connect"))
    )
    (net (code "106") (name "unconnected-(U315A-PD6{slash}SYNC{slash}RXD1{slash}MISO-Pad32)") (class "Default")
      (node (ref "U315") (pin "32") (pinfunction "PD6/SYNC/RXD1/MISO_32") (pintype "bidirectional+no_connect"))
    )
    (net (code "107") (name "unconnected-(U315A-PD7{slash}SYNC{slash}TXD1{slash}SCK{slash}CLKOUT{slash}EVOUT-Pad33)") (class "Default")
      (node (ref "U315") (pin "33") (pinfunction "PD7/SYNC/TXD1/SCK/CLKOUT/EVOUT_33") (pintype "bidirectional+no_connect"))
    )
    (net (code "108") (name "unconnected-(U315A-PE2{slash}SYNC{slash}ASYNC{slash}OC0C{slash}RXD0-Pad38)") (class "Default")
      (node (ref "U315") (pin "38") (pinfunction "PE2/SYNC/ASYNC/OC0C/RXD0_38") (pintype "bidirectional"))
    )
    (net (code "109") (name "unconnected-(U315A-PE3{slash}SYNC{slash}OC0D{slash}TXD0-Pad39)") (class "Default")
      (node (ref "U315") (pin "39") (pinfunction "PE3/SYNC/OC0D/TXD0_39") (pintype "bidirectional"))
    )
    (net (code "110") (name "unconnected-(U315A-PE4{slash}SYNC{slash}OC1A{slash}SS-Pad40)") (class "Default")
      (node (ref "U315") (pin "40") (pinfunction "PE4/SYNC/OC1A/SS_40") (pintype "bidirectional+no_connect"))
    )
    (net (code "111") (name "unconnected-(U315A-PE5{slash}SYNC{slash}OC1B{slash}XCK1{slash}MOSI-Pad41)") (class "Default")
      (node (ref "U315") (pin "41") (pinfunction "PE5/SYNC/OC1B/XCK1/MOSI_41") (pintype "bidirectional+no_connect"))
    )
    (net (code "112") (name "unconnected-(U315A-PE6{slash}SYNC{slash}RXD1{slash}MISO{slash}TOSC2-Pad42)") (class "Default")
      (node (ref "U315") (pin "42") (pinfunction "PE6/SYNC/RXD1/MISO/TOSC2_42") (pintype "bidirectional+no_connect"))
    )
    (net (code "113") (name "unconnected-(U315A-PE7{slash}SYNC{slash}TXD1{slash}SCK{slash}CLKOUT{slash}EVOUT{slash}TOSC1-Pad43)") (class "Default")
      (node (ref "U315") (pin "43") (pinfunction "PE7/SYNC/TXD1/SCK/CLKOUT/EVOUT/TOSC1_43") (pintype "bidirectional+no_connect"))
    )
    (net (code "114") (name "unconnected-(U315A-PF7{slash}SYNC-Pad55)") (class "Default")
      (node (ref "U315") (pin "55") (pinfunction "PF7/SYNC_55") (pintype "bidirectional+no_connect"))
    )
    (net (code "115") (name "unconnected-(U317C-Y-Pad10)") (class "Default")
      (node (ref "U317") (pin "10") (pinfunction "Y_10") (pintype "output+no_connect"))
    )
    (net (code "116") (name "unconnected-(U317D-Y-Pad13)") (class "Default")
      (node (ref "U317") (pin "13") (pinfunction "Y_13") (pintype "output+no_connect"))
    )
  )
)
